# 2.net
KiCad netlist of a schematic drawn in Altium Designer
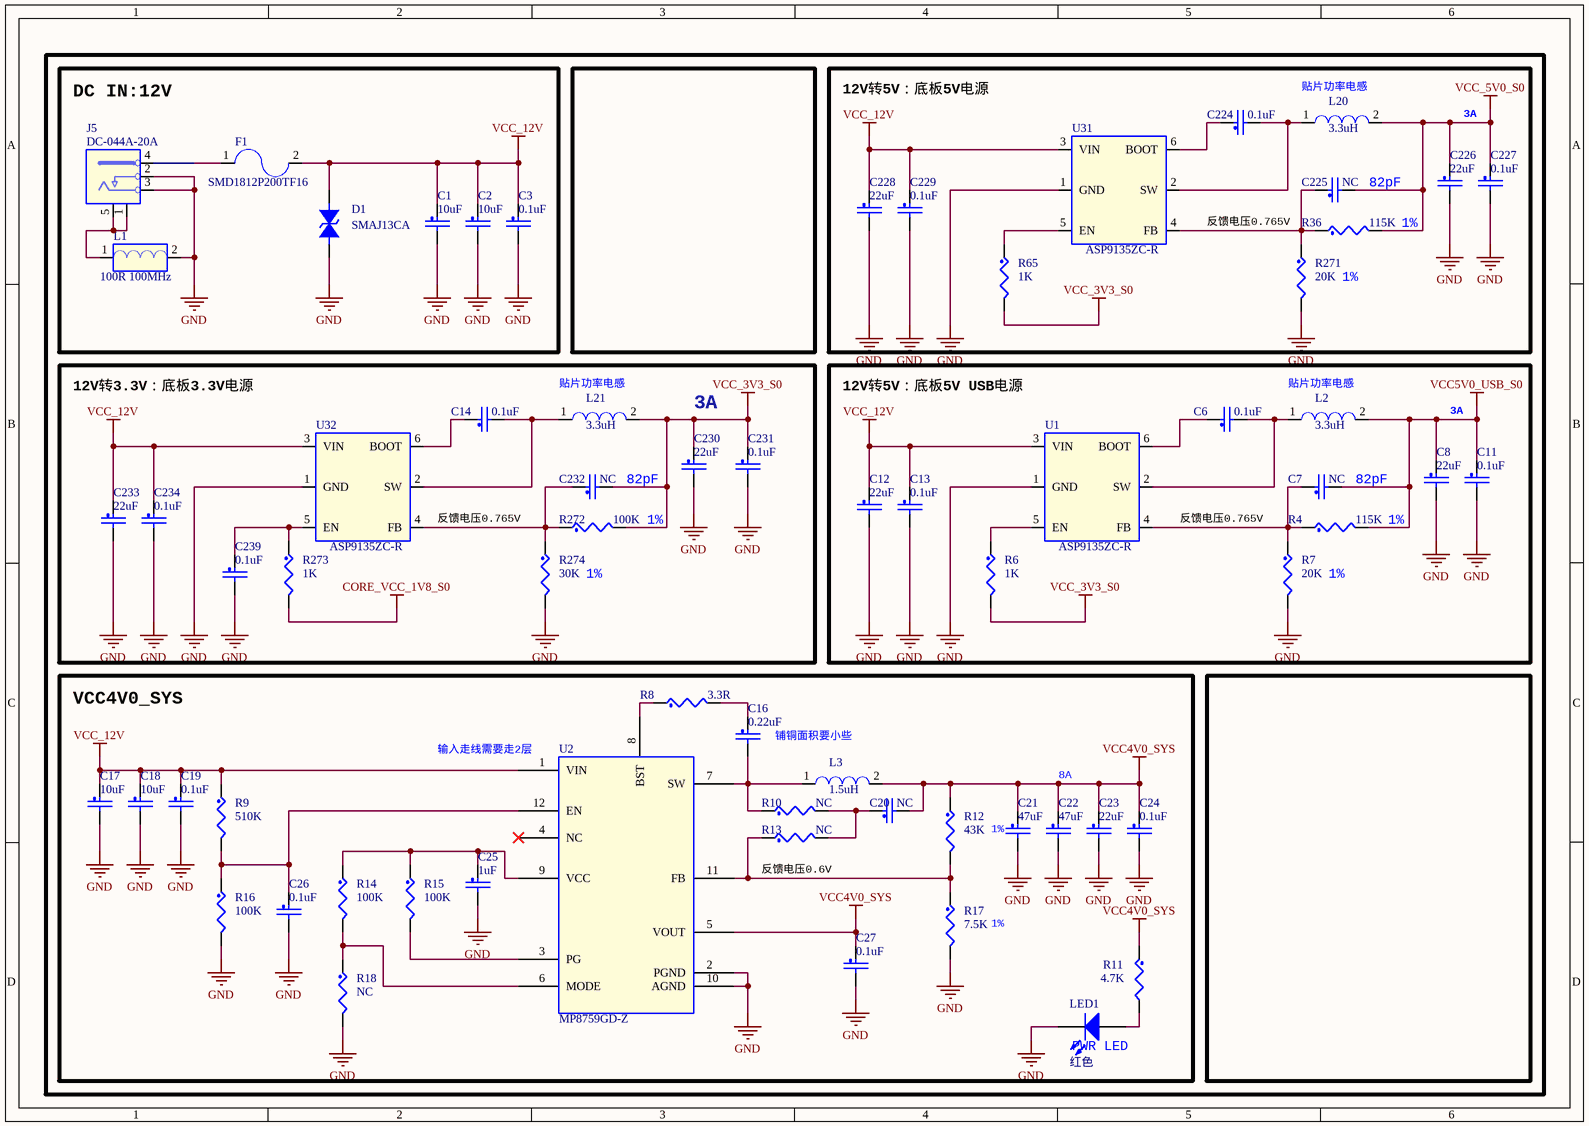
[diagram p0: 2.电源.SchDoc]

(export (version "E")
  (design (tool "Eeschema 10.0.6"))
  (components
    (comp (ref "C1") (value "10uF") (footprint "0.PCB1:C0603") (libsource (lib "RK3588底板") (part "CAP_NP")))
    (comp (ref "C2") (value "10uF") (footprint "0.PCB1:C0603") (libsource (lib "RK3588底板") (part "CAP_NP")))
    (comp (ref "C3") (value "0.1uF") (footprint "0.PCB1:C0402") (libsource (lib "RK3588底板") (part "CAP_NP")))
    (comp (ref "C6") (value "0.1uF") (footprint "0.PCB1:C0402") (libsource (lib "RK3588底板") (part "CAP_NP")))
    (comp (ref "C7") (value "NC") (footprint "0.PCB1:C0402") (libsource (lib "RK3588底板") (part "CAP_NP")))
    (comp (ref "C8") (value "22uF") (footprint "0.PCB1:C0805") (libsource (lib "RK3588底板") (part "CAP_NP")))
    (comp (ref "C11") (value "0.1uF") (footprint "0.PCB1:C0402") (libsource (lib "RK3588底板") (part "CAP_NP")))
    (comp (ref "C12") (value "22uF") (footprint "0.PCB1:C0805") (libsource (lib "RK3588底板") (part "CAP_NP")))
    (comp (ref "C13") (value "0.1uF") (footprint "0.PCB1:C0402") (libsource (lib "RK3588底板") (part "CAP_NP")))
    (comp (ref "C14") (value "0.1uF") (footprint "0.PCB1:C0402") (libsource (lib "RK3588底板") (part "CAP_NP")))
    (comp (ref "C16")
      (value "0.22uF")
      (footprint "0.PCB1:C0402")
      (libsource (lib "RK3588底板") (part "CAP_NP"))
    )
    (comp (ref "C17") (value "10uF") (footprint "0.PCB1:C0603") (libsource (lib "RK3588底板") (part "CAP_NP")))
    (comp (ref "C18") (value "10uF") (footprint "0.PCB1:C0603") (libsource (lib "RK3588底板") (part "CAP_NP")))
    (comp (ref "C19") (value "0.1uF") (footprint "0.PCB1:C0402") (libsource (lib "RK3588底板") (part "CAP_NP")))
    (comp (ref "C20") (value "NC") (footprint "0.PCB1:C0402") (libsource (lib "RK3588底板") (part "CAP_NP")))
    (comp (ref "C21") (value "47uF") (footprint "0.PCB1:C0805") (libsource (lib "RK3588底板") (part "CAP_NP")))
    (comp (ref "C22") (value "47uF") (footprint "0.PCB1:C0805") (libsource (lib "RK3588底板") (part "CAP_NP")))
    (comp (ref "C23") (value "22uF") (footprint "0.PCB1:C0603") (libsource (lib "RK3588底板") (part "CAP_NP")))
    (comp (ref "C24") (value "0.1uF") (footprint "0.PCB1:C0402") (libsource (lib "RK3588底板") (part "CAP_NP")))
    (comp (ref "C25") (value "1uF") (footprint "0.PCB1:C0402") (libsource (lib "RK3588底板") (part "CAP_NP")))
    (comp (ref "C26") (value "0.1uF") (footprint "0.PCB1:C0402") (libsource (lib "RK3588底板") (part "CAP_NP")))
    (comp (ref "C27") (value "0.1uF") (footprint "0.PCB1:C0402") (libsource (lib "RK3588底板") (part "CAP_NP")))
    (comp (ref "C224")
      (value "0.1uF")
      (footprint "0.PCB1:C0402")
      (libsource (lib "RK3588底板") (part "CAP_NP"))
    )
    (comp (ref "C225") (value "NC") (footprint "0.PCB1:C0402") (libsource (lib "RK3588底板") (part "CAP_NP")))
    (comp (ref "C226") (value "22uF") (footprint "0.PCB1:C0805") (libsource (lib "RK3588底板") (part "CAP_NP")))
    (comp (ref "C227")
      (value "0.1uF")
      (footprint "0.PCB1:C0402")
      (libsource (lib "RK3588底板") (part "CAP_NP"))
    )
    (comp (ref "C228") (value "22uF") (footprint "0.PCB1:C0805") (libsource (lib "RK3588底板") (part "CAP_NP")))
    (comp (ref "C229")
      (value "0.1uF")
      (footprint "0.PCB1:C0402")
      (libsource (lib "RK3588底板") (part "CAP_NP"))
    )
    (comp (ref "C230") (value "22uF") (footprint "0.PCB1:C0805") (libsource (lib "RK3588底板") (part "CAP_NP")))
    (comp (ref "C231")
      (value "0.1uF")
      (footprint "0.PCB1:C0402")
      (libsource (lib "RK3588底板") (part "CAP_NP"))
    )
    (comp (ref "C232") (value "NC") (footprint "0.PCB1:C0402") (libsource (lib "RK3588底板") (part "CAP_NP")))
    (comp (ref "C233") (value "22uF") (footprint "0.PCB1:C0805") (libsource (lib "RK3588底板") (part "CAP_NP")))
    (comp (ref "C234")
      (value "0.1uF")
      (footprint "0.PCB1:C0402")
      (libsource (lib "RK3588底板") (part "CAP_NP"))
    )
    (comp (ref "C239")
      (value "0.1uF")
      (footprint "0.PCB1:C0402")
      (libsource (lib "RK3588底板") (part "CAP_NP"))
    )
    (comp (ref "D1")
      (value "SMAJ13CA")
      (footprint "0.PCB1:SMA_CA")
      (libsource (lib "RK3588底板") (part "DIODE BI-DIR TRIG"))
    )
    (comp (ref "F1")
      (value "SMD1812P200TF16")
      (footprint "0.PCB1:F1812")
      (libsource (lib "RK3588底板") (part "FUSE"))
    )
    (comp (ref "J5")
      (value "DC-044A-20A")
      (footprint "0.PCB1:dc_in_th_3p_10r1x11r6")
      (libsource (lib "RK3588底板") (part "DC-044A-20A"))
    )
    (comp (ref "L1")
      (value "100R 100MHz")
      (footprint "0.PCB1:L0603")
      (libsource (lib "RK3588底板") (part "BEAD"))
    )
    (comp (ref "L2") (value "3.3uH") (footprint "0.PCB1:l4520") (libsource (lib "RK3588底板") (part "IND")))
    (comp (ref "L3") (value "1.5uH") (footprint "0.PCB1:L0518") (libsource (lib "RK3588底板") (part "IND")))
    (comp (ref "L20") (value "3.3uH") (footprint "0.PCB1:l4520") (libsource (lib "RK3588底板") (part "IND")))
    (comp (ref "L21") (value "3.3uH") (footprint "0.PCB1:l4520") (libsource (lib "RK3588底板") (part "IND")))
    (comp (ref "LED1")
      (value "红色")
      (footprint "0.PCB1:LED0603_R")
      (description "贴片LED")
      (libsource (lib "RK3588底板") (part "LED"))
    )
    (comp (ref "R4") (value "115K") (footprint "0.PCB1:R0402") (libsource (lib "RK3588底板") (part "RES")))
    (comp (ref "R6") (value "1K") (footprint "0.PCB1:R0402") (libsource (lib "RK3588底板") (part "RES")))
    (comp (ref "R7") (value "20K") (footprint "0.PCB1:R0402") (libsource (lib "RK3588底板") (part "RES")))
    (comp (ref "R8") (value "3.3R") (footprint "0.PCB1:R0402") (libsource (lib "RK3588底板") (part "RES")))
    (comp (ref "R9") (value "510K") (footprint "0.PCB1:R0402") (libsource (lib "RK3588底板") (part "RES")))
    (comp (ref "R10") (value "NC") (footprint "0.PCB1:R0402") (libsource (lib "RK3588底板") (part "RES")))
    (comp (ref "R11") (value "4.7K") (footprint "0.PCB1:R0402") (libsource (lib "RK3588底板") (part "RES")))
    (comp (ref "R12") (value "43K") (footprint "0.PCB1:R0402") (libsource (lib "RK3588底板") (part "RES")))
    (comp (ref "R13") (value "NC") (footprint "0.PCB1:R0402") (libsource (lib "RK3588底板") (part "RES")))
    (comp (ref "R14") (value "100K") (footprint "0.PCB1:R0402") (libsource (lib "RK3588底板") (part "RES")))
    (comp (ref "R15") (value "100K") (footprint "0.PCB1:R0402") (libsource (lib "RK3588底板") (part "RES")))
    (comp (ref "R16") (value "100K") (footprint "0.PCB1:R0402") (libsource (lib "RK3588底板") (part "RES")))
    (comp (ref "R17") (value "7.5K") (footprint "0.PCB1:R0402") (libsource (lib "RK3588底板") (part "RES")))
    (comp (ref "R18") (value "NC") (footprint "0.PCB1:R0402") (libsource (lib "RK3588底板") (part "RES")))
    (comp (ref "R36") (value "115K") (footprint "0.PCB1:R0402") (libsource (lib "RK3588底板") (part "RES")))
    (comp (ref "R65") (value "1K") (footprint "0.PCB1:R0402") (libsource (lib "RK3588底板") (part "RES")))
    (comp (ref "R271") (value "20K") (footprint "0.PCB1:R0402") (libsource (lib "RK3588底板") (part "RES")))
    (comp (ref "R272") (value "100K") (footprint "0.PCB1:R0402") (libsource (lib "RK3588底板") (part "RES")))
    (comp (ref "R273") (value "1K") (footprint "0.PCB1:R0402") (libsource (lib "RK3588底板") (part "RES")))
    (comp (ref "R274") (value "30K") (footprint "0.PCB1:R0402") (libsource (lib "RK3588底板") (part "RES")))
    (comp (ref "U1")
      (value "ASP9135ZC-R")
      (footprint "0.PCB1:SOT23_6")
      (libsource (lib "RK3588底板") (part "TP6327GS6"))
    )
    (comp (ref "U2")
      (value "MP8759GD-Z")
      (footprint "0.PCB1:QFN12-2R00X3R00")
      (libsource (lib "RK3588底板") (part "MP8759GD-Z"))
    )
    (comp (ref "U31")
      (value "ASP9135ZC-R")
      (footprint "0.PCB1:SOT23_6")
      (libsource (lib "RK3588底板") (part "TP6327GS6"))
    )
    (comp (ref "U32")
      (value "ASP9135ZC-R")
      (footprint "0.PCB1:SOT23_6")
      (libsource (lib "RK3588底板") (part "TP6327GS6"))
    )
  )
  (nets
    (net (code "1") (name "CORE_VCC_1V8_S0") (class "Default")
      (node (ref "R273") (pin "2") (pinfunction "2_2") (pintype "passive"))
    )
    (net (code "2") (name "GND") (class "Default")
      (node (ref "C1") (pin "2") (pinfunction "2_2") (pintype "passive"))
      (node (ref "C11") (pin "2") (pinfunction "2_2") (pintype "passive"))
      (node (ref "C12") (pin "2") (pinfunction "2_2") (pintype "passive"))
      (node (ref "C13") (pin "2") (pinfunction "2_2") (pintype "passive"))
      (node (ref "C17") (pin "2") (pinfunction "2_2") (pintype "passive"))
      (node (ref "C18") (pin "2") (pinfunction "2_2") (pintype "passive"))
      (node (ref "C19") (pin "2") (pinfunction "2_2") (pintype "passive"))
      (node (ref "C2") (pin "2") (pinfunction "2_2") (pintype "passive"))
      (node (ref "C21") (pin "2") (pinfunction "2_2") (pintype "passive"))
      (node (ref "C22") (pin "2") (pinfunction "2_2") (pintype "passive"))
      (node (ref "C226") (pin "2") (pinfunction "2_2") (pintype "passive"))
      (node (ref "C227") (pin "2") (pinfunction "2_2") (pintype "passive"))
      (node (ref "C228") (pin "2") (pinfunction "2_2") (pintype "passive"))
      (node (ref "C229") (pin "2") (pinfunction "2_2") (pintype "passive"))
      (node (ref "C23") (pin "2") (pinfunction "2_2") (pintype "passive"))
      (node (ref "C230") (pin "2") (pinfunction "2_2") (pintype "passive"))
      (node (ref "C231") (pin "2") (pinfunction "2_2") (pintype "passive"))
      (node (ref "C233") (pin "2") (pinfunction "2_2") (pintype "passive"))
      (node (ref "C234") (pin "2") (pinfunction "2_2") (pintype "passive"))
      (node (ref "C239") (pin "2") (pinfunction "2_2") (pintype "passive"))
      (node (ref "C24") (pin "2") (pinfunction "2_2") (pintype "passive"))
      (node (ref "C25") (pin "2") (pinfunction "2_2") (pintype "passive"))
      (node (ref "C26") (pin "2") (pinfunction "2_2") (pintype "passive"))
      (node (ref "C27") (pin "2") (pinfunction "2_2") (pintype "passive"))
      (node (ref "C3") (pin "2") (pinfunction "2_2") (pintype "passive"))
      (node (ref "C8") (pin "2") (pinfunction "2_2") (pintype "passive"))
      (node (ref "D1") (pin "1") (pinfunction "1_1") (pintype "passive"))
      (node (ref "J5") (pin "2") (pinfunction "2_2") (pintype "passive"))
      (node (ref "J5") (pin "3") (pinfunction "3_3") (pintype "passive"))
      (node (ref "L1") (pin "2") (pinfunction "2_2") (pintype "passive"))
      (node (ref "LED1") (pin "2") (pinfunction "K_2") (pintype "passive"))
      (node (ref "R16") (pin "2") (pinfunction "2_2") (pintype "passive"))
      (node (ref "R17") (pin "2") (pinfunction "2_2") (pintype "passive"))
      (node (ref "R18") (pin "2") (pinfunction "2_2") (pintype "passive"))
      (node (ref "R271") (pin "2") (pinfunction "2_2") (pintype "passive"))
      (node (ref "R274") (pin "2") (pinfunction "2_2") (pintype "passive"))
      (node (ref "R7") (pin "2") (pinfunction "2_2") (pintype "passive"))
      (node (ref "U1") (pin "1") (pinfunction "GND_1") (pintype "passive"))
      (node (ref "U2") (pin "10") (pinfunction "AGND_10") (pintype "passive"))
      (node (ref "U2") (pin "2") (pinfunction "PGND_2") (pintype "passive"))
      (node (ref "U31") (pin "1") (pinfunction "GND_1") (pintype "passive"))
      (node (ref "U32") (pin "1") (pinfunction "GND_1") (pintype "passive"))
    )
    (net (code "3") (name "Net-(C16-Pad1)") (class "Default")
      (node (ref "C16") (pin "1") (pinfunction "1_1") (pintype "passive"))
      (node (ref "R8") (pin "2") (pinfunction "2_2") (pintype "passive"))
    )
    (net (code "4") (name "Net-(C20-Pad1)") (class "Default")
      (node (ref "C20") (pin "1") (pinfunction "1_1") (pintype "passive"))
      (node (ref "R10") (pin "2") (pinfunction "2_2") (pintype "passive"))
      (node (ref "R13") (pin "2") (pinfunction "2_2") (pintype "passive"))
    )
    (net (code "5") (name "Net-(F1-Pad1)") (class "Default")
      (node (ref "F1") (pin "1") (pinfunction "1_1") (pintype "passive"))
      (node (ref "J5") (pin "4") (pinfunction "4_4") (pintype "passive"))
    )
    (net (code "6") (name "Net-(J5-Pad1)") (class "Default")
      (node (ref "J5") (pin "1") (pinfunction "1_1") (pintype "passive"))
      (node (ref "J5") (pin "5") (pinfunction "5_5") (pintype "passive"))
      (node (ref "L1") (pin "1") (pinfunction "1_1") (pintype "passive"))
    )
    (net (code "7") (name "Net-(LED1-A)") (class "Default")
      (node (ref "LED1") (pin "1") (pinfunction "A_1") (pintype "passive"))
      (node (ref "R11") (pin "2") (pinfunction "2_2") (pintype "passive"))
    )
    (net (code "8") (name "Net-(U1-BOOT)") (class "Default")
      (node (ref "C6") (pin "1") (pinfunction "1_1") (pintype "passive"))
      (node (ref "U1") (pin "6") (pinfunction "BOOT_6") (pintype "passive"))
    )
    (net (code "9") (name "Net-(U1-EN)") (class "Default")
      (node (ref "R6") (pin "1") (pinfunction "1_1") (pintype "passive"))
      (node (ref "U1") (pin "5") (pinfunction "EN_5") (pintype "passive"))
    )
    (net (code "10") (name "Net-(U1-FB)") (class "Default")
      (node (ref "C7") (pin "1") (pinfunction "1_1") (pintype "passive"))
      (node (ref "R4") (pin "1") (pinfunction "1_1") (pintype "passive"))
      (node (ref "R7") (pin "1") (pinfunction "1_1") (pintype "passive"))
      (node (ref "U1") (pin "4") (pinfunction "FB_4") (pintype "passive"))
    )
    (net (code "11") (name "Net-(U1-SW)") (class "Default")
      (node (ref "C6") (pin "2") (pinfunction "2_2") (pintype "passive"))
      (node (ref "L2") (pin "1") (pinfunction "1_1") (pintype "passive"))
      (node (ref "U1") (pin "2") (pinfunction "SW_2") (pintype "passive"))
    )
    (net (code "12") (name "Net-(U2-BST)") (class "Default")
      (node (ref "R8") (pin "1") (pinfunction "1_1") (pintype "passive"))
      (node (ref "U2") (pin "8") (pinfunction "BST_8") (pintype "passive"))
    )
    (net (code "13") (name "Net-(U2-EN)") (class "Default")
      (node (ref "C26") (pin "1") (pinfunction "1_1") (pintype "passive"))
      (node (ref "R16") (pin "1") (pinfunction "1_1") (pintype "passive"))
      (node (ref "R9") (pin "2") (pinfunction "2_2") (pintype "passive"))
      (node (ref "U2") (pin "12") (pinfunction "EN_12") (pintype "passive"))
    )
    (net (code "14") (name "Net-(U2-FB)") (class "Default")
      (node (ref "R12") (pin "2") (pinfunction "2_2") (pintype "passive"))
      (node (ref "R13") (pin "1") (pinfunction "1_1") (pintype "passive"))
      (node (ref "R17") (pin "1") (pinfunction "1_1") (pintype "passive"))
      (node (ref "U2") (pin "11") (pinfunction "FB_11") (pintype "passive"))
    )
    (net (code "15") (name "Net-(U2-MODE)") (class "Default")
      (node (ref "R14") (pin "2") (pinfunction "2_2") (pintype "passive"))
      (node (ref "R18") (pin "1") (pinfunction "1_1") (pintype "passive"))
      (node (ref "U2") (pin "6") (pinfunction "MODE_6") (pintype "passive"))
    )
    (net (code "16") (name "Net-(U2-PG)") (class "Default")
      (node (ref "R15") (pin "2") (pinfunction "2_2") (pintype "passive"))
      (node (ref "U2") (pin "3") (pinfunction "PG_3") (pintype "passive"))
    )
    (net (code "17") (name "Net-(U2-SW)") (class "Default")
      (node (ref "C16") (pin "2") (pinfunction "2_2") (pintype "passive"))
      (node (ref "L3") (pin "1") (pinfunction "1_1") (pintype "passive"))
      (node (ref "R10") (pin "1") (pinfunction "1_1") (pintype "passive"))
      (node (ref "U2") (pin "7") (pinfunction "SW_7") (pintype "passive"))
    )
    (net (code "18") (name "Net-(U2-VCC)") (class "Default")
      (node (ref "C25") (pin "1") (pinfunction "1_1") (pintype "passive"))
      (node (ref "R14") (pin "1") (pinfunction "1_1") (pintype "passive"))
      (node (ref "R15") (pin "1") (pinfunction "1_1") (pintype "passive"))
      (node (ref "U2") (pin "9") (pinfunction "VCC_9") (pintype "passive"))
    )
    (net (code "19") (name "Net-(U31-BOOT)") (class "Default")
      (node (ref "C224") (pin "1") (pinfunction "1_1") (pintype "passive"))
      (node (ref "U31") (pin "6") (pinfunction "BOOT_6") (pintype "passive"))
    )
    (net (code "20") (name "Net-(U31-EN)") (class "Default")
      (node (ref "R65") (pin "1") (pinfunction "1_1") (pintype "passive"))
      (node (ref "U31") (pin "5") (pinfunction "EN_5") (pintype "passive"))
    )
    (net (code "21") (name "Net-(U31-FB)") (class "Default")
      (node (ref "C225") (pin "1") (pinfunction "1_1") (pintype "passive"))
      (node (ref "R271") (pin "1") (pinfunction "1_1") (pintype "passive"))
      (node (ref "R36") (pin "1") (pinfunction "1_1") (pintype "passive"))
      (node (ref "U31") (pin "4") (pinfunction "FB_4") (pintype "passive"))
    )
    (net (code "22") (name "Net-(U31-SW)") (class "Default")
      (node (ref "C224") (pin "2") (pinfunction "2_2") (pintype "passive"))
      (node (ref "L20") (pin "1") (pinfunction "1_1") (pintype "passive"))
      (node (ref "U31") (pin "2") (pinfunction "SW_2") (pintype "passive"))
    )
    (net (code "23") (name "Net-(U32-BOOT)") (class "Default")
      (node (ref "C14") (pin "1") (pinfunction "1_1") (pintype "passive"))
      (node (ref "U32") (pin "6") (pinfunction "BOOT_6") (pintype "passive"))
    )
    (net (code "24") (name "Net-(U32-EN)") (class "Default")
      (node (ref "C239") (pin "1") (pinfunction "1_1") (pintype "passive"))
      (node (ref "R273") (pin "1") (pinfunction "1_1") (pintype "passive"))
      (node (ref "U32") (pin "5") (pinfunction "EN_5") (pintype "passive"))
    )
    (net (code "25") (name "Net-(U32-FB)") (class "Default")
      (node (ref "C232") (pin "1") (pinfunction "1_1") (pintype "passive"))
      (node (ref "R272") (pin "1") (pinfunction "1_1") (pintype "passive"))
      (node (ref "R274") (pin "1") (pinfunction "1_1") (pintype "passive"))
      (node (ref "U32") (pin "4") (pinfunction "FB_4") (pintype "passive"))
    )
    (net (code "26") (name "Net-(U32-SW)") (class "Default")
      (node (ref "C14") (pin "2") (pinfunction "2_2") (pintype "passive"))
      (node (ref "L21") (pin "1") (pinfunction "1_1") (pintype "passive"))
      (node (ref "U32") (pin "2") (pinfunction "SW_2") (pintype "passive"))
    )
    (net (code "27") (name "VCC4V0_SYS") (class "Default")
      (node (ref "C20") (pin "2") (pinfunction "2_2") (pintype "passive"))
      (node (ref "C21") (pin "1") (pinfunction "1_1") (pintype "passive"))
      (node (ref "C22") (pin "1") (pinfunction "1_1") (pintype "passive"))
      (node (ref "C23") (pin "1") (pinfunction "1_1") (pintype "passive"))
      (node (ref "C24") (pin "1") (pinfunction "1_1") (pintype "passive"))
      (node (ref "C27") (pin "1") (pinfunction "1_1") (pintype "passive"))
      (node (ref "L3") (pin "2") (pinfunction "2_2") (pintype "passive"))
      (node (ref "R11") (pin "1") (pinfunction "1_1") (pintype "passive"))
      (node (ref "R12") (pin "1") (pinfunction "1_1") (pintype "passive"))
      (node (ref "U2") (pin "5") (pinfunction "VOUT_5") (pintype "passive"))
    )
    (net (code "28") (name "VCC5V0_USB_S0") (class "Default")
      (node (ref "C11") (pin "1") (pinfunction "1_1") (pintype "passive"))
      (node (ref "C7") (pin "2") (pinfunction "2_2") (pintype "passive"))
      (node (ref "C8") (pin "1") (pinfunction "1_1") (pintype "passive"))
      (node (ref "L2") (pin "2") (pinfunction "2_2") (pintype "passive"))
      (node (ref "R4") (pin "2") (pinfunction "2_2") (pintype "passive"))
    )
    (net (code "29") (name "VCC_3V3_S0") (class "Default")
      (node (ref "C230") (pin "1") (pinfunction "1_1") (pintype "passive"))
      (node (ref "C231") (pin "1") (pinfunction "1_1") (pintype "passive"))
      (node (ref "C232") (pin "2") (pinfunction "2_2") (pintype "passive"))
      (node (ref "L21") (pin "2") (pinfunction "2_2") (pintype "passive"))
      (node (ref "R272") (pin "2") (pinfunction "2_2") (pintype "passive"))
      (node (ref "R6") (pin "2") (pinfunction "2_2") (pintype "passive"))
      (node (ref "R65") (pin "2") (pinfunction "2_2") (pintype "passive"))
    )
    (net (code "30") (name "VCC_5V0_S0") (class "Default")
      (node (ref "C225") (pin "2") (pinfunction "2_2") (pintype "passive"))
      (node (ref "C226") (pin "1") (pinfunction "1_1") (pintype "passive"))
      (node (ref "C227") (pin "1") (pinfunction "1_1") (pintype "passive"))
      (node (ref "L20") (pin "2") (pinfunction "2_2") (pintype "passive"))
      (node (ref "R36") (pin "2") (pinfunction "2_2") (pintype "passive"))
    )
    (net (code "31") (name "VCC_12V") (class "Default")
      (node (ref "C1") (pin "1") (pinfunction "1_1") (pintype "passive"))
      (node (ref "C12") (pin "1") (pinfunction "1_1") (pintype "passive"))
      (node (ref "C13") (pin "1") (pinfunction "1_1") (pintype "passive"))
      (node (ref "C17") (pin "1") (pinfunction "1_1") (pintype "passive"))
      (node (ref "C18") (pin "1") (pinfunction "1_1") (pintype "passive"))
      (node (ref "C19") (pin "1") (pinfunction "1_1") (pintype "passive"))
      (node (ref "C2") (pin "1") (pinfunction "1_1") (pintype "passive"))
      (node (ref "C228") (pin "1") (pinfunction "1_1") (pintype "passive"))
      (node (ref "C229") (pin "1") (pinfunction "1_1") (pintype "passive"))
      (node (ref "C233") (pin "1") (pinfunction "1_1") (pintype "passive"))
      (node (ref "C234") (pin "1") (pinfunction "1_1") (pintype "passive"))
      (node (ref "C3") (pin "1") (pinfunction "1_1") (pintype "passive"))
      (node (ref "D1") (pin "2") (pinfunction "2_2") (pintype "passive"))
      (node (ref "F1") (pin "2") (pinfunction "2_2") (pintype "passive"))
      (node (ref "R9") (pin "1") (pinfunction "1_1") (pintype "passive"))
      (node (ref "U1") (pin "3") (pinfunction "VIN_3") (pintype "passive"))
      (node (ref "U2") (pin "1") (pinfunction "VIN_1") (pintype "passive"))
      (node (ref "U31") (pin "3") (pinfunction "VIN_3") (pintype "passive"))
      (node (ref "U32") (pin "3") (pinfunction "VIN_3") (pintype "passive"))
    )
    (net (code "32") (name "unconnected-(U2-NC-Pad4)") (class "Default")
      (node (ref "U2") (pin "4") (pinfunction "NC_4") (pintype "passive+no_connect"))
    )
  )
)
